# TempHumiditySensorRaspberryPi.net
KiCad netlist of a schematic drawn in EAGLE
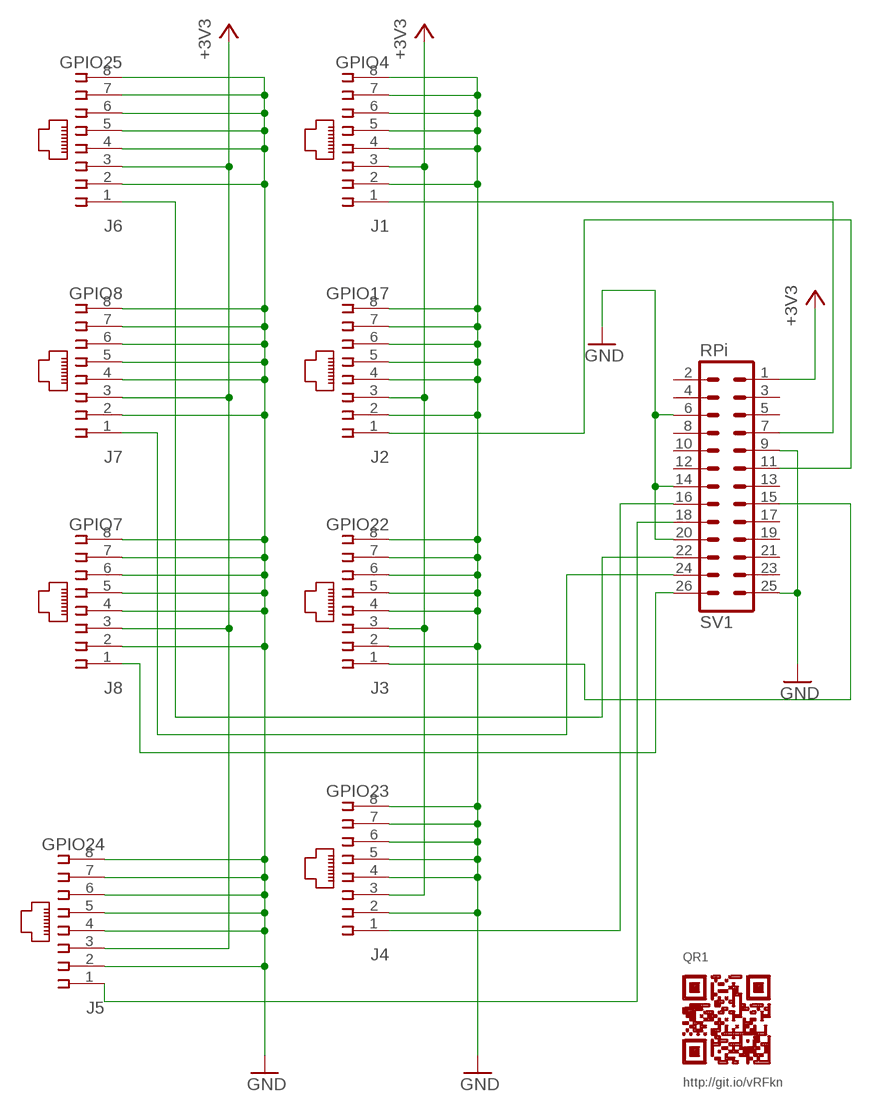
[diagram p0: schematic, sheet 1]

(export (version "E")
  (design (tool "Eeschema 10.0.6"))
  (components
    (comp (ref "J1")
      (value "GPIO4")
      (footprint "eagle-import:555164-1")
      (fields (field (name "PARTNO") "5555164-1"))
      (libsource (lib "eagle-import") (part "555164-1"))
    )
    (comp (ref "J2")
      (value "GPIO17")
      (footprint "eagle-import:555164-1")
      (fields (field (name "PARTNO") "5555164-1"))
      (libsource (lib "eagle-import") (part "555164-1"))
    )
    (comp (ref "J3")
      (value "GPIO22")
      (footprint "eagle-import:555164-1")
      (fields (field (name "PARTNO") "5555164-1"))
      (libsource (lib "eagle-import") (part "555164-1"))
    )
    (comp (ref "J4")
      (value "GPIO23")
      (footprint "eagle-import:555164-1")
      (fields (field (name "PARTNO") "5555164-1"))
      (libsource (lib "eagle-import") (part "555164-1"))
    )
    (comp (ref "J5")
      (value "GPIO24")
      (footprint "eagle-import:555164-1")
      (fields (field (name "PARTNO") "5555164-1"))
      (libsource (lib "eagle-import") (part "555164-1"))
    )
    (comp (ref "J6")
      (value "GPIO25")
      (footprint "eagle-import:555164-1")
      (fields (field (name "PARTNO") "5555164-1"))
      (libsource (lib "eagle-import") (part "555164-1"))
    )
    (comp (ref "J7")
      (value "GPIO8")
      (footprint "eagle-import:555164-1")
      (fields (field (name "PARTNO") "5555164-1"))
      (libsource (lib "eagle-import") (part "555164-1"))
    )
    (comp (ref "J8")
      (value "GPIO7")
      (footprint "eagle-import:555164-1")
      (fields (field (name "PARTNO") "5555164-1"))
      (libsource (lib "eagle-import") (part "555164-1"))
    )
    (comp (ref "QR1")
      (value "QR-HTTP://GIT.IO/VRFKN")
      (footprint "eagle-import:QR-HTTP___GIT.IO_VRFKN")
      (libsource (lib "eagle-import") (part "QR-HTTP{colon}//GIT.IO/VRFKN"))
    )
    (comp (ref "SV1")
      (value "RPi")
      (footprint "eagle-import:ML26")
      (fields (field (name "PARTNO") "SBH11-PBPC-D13-ST-BK"))
      (libsource (lib "eagle-import") (part "ML26"))
    )
  )
  (nets
    (net (code "1") (name "+3V3") (class "Default")
      (node (ref "J1") (pin "3") (pinfunction "3_3") (pintype "passive"))
      (node (ref "J2") (pin "3") (pinfunction "3_3") (pintype "passive"))
      (node (ref "J3") (pin "3") (pinfunction "3_3") (pintype "passive"))
      (node (ref "J4") (pin "3") (pinfunction "3_3") (pintype "passive"))
      (node (ref "J5") (pin "3") (pinfunction "3_3") (pintype "passive"))
      (node (ref "J6") (pin "3") (pinfunction "3_3") (pintype "passive"))
      (node (ref "J7") (pin "3") (pinfunction "3_3") (pintype "passive"))
      (node (ref "J8") (pin "3") (pinfunction "3_3") (pintype "passive"))
      (node (ref "SV1") (pin "1") (pinfunction "1_1") (pintype "passive"))
    )
    (net (code "2") (name "GND") (class "Default")
      (node (ref "J1") (pin "2") (pinfunction "2_2") (pintype "passive"))
      (node (ref "J1") (pin "4") (pinfunction "4_4") (pintype "passive"))
      (node (ref "J1") (pin "5") (pinfunction "5_5") (pintype "passive"))
      (node (ref "J1") (pin "6") (pinfunction "6_6") (pintype "passive"))
      (node (ref "J1") (pin "7") (pinfunction "7_7") (pintype "passive"))
      (node (ref "J1") (pin "8") (pinfunction "8_8") (pintype "passive"))
      (node (ref "J2") (pin "2") (pinfunction "2_2") (pintype "passive"))
      (node (ref "J2") (pin "4") (pinfunction "4_4") (pintype "passive"))
      (node (ref "J2") (pin "5") (pinfunction "5_5") (pintype "passive"))
      (node (ref "J2") (pin "6") (pinfunction "6_6") (pintype "passive"))
      (node (ref "J2") (pin "7") (pinfunction "7_7") (pintype "passive"))
      (node (ref "J2") (pin "8") (pinfunction "8_8") (pintype "passive"))
      (node (ref "J3") (pin "2") (pinfunction "2_2") (pintype "passive"))
      (node (ref "J3") (pin "4") (pinfunction "4_4") (pintype "passive"))
      (node (ref "J3") (pin "5") (pinfunction "5_5") (pintype "passive"))
      (node (ref "J3") (pin "6") (pinfunction "6_6") (pintype "passive"))
      (node (ref "J3") (pin "7") (pinfunction "7_7") (pintype "passive"))
      (node (ref "J3") (pin "8") (pinfunction "8_8") (pintype "passive"))
      (node (ref "J4") (pin "2") (pinfunction "2_2") (pintype "passive"))
      (node (ref "J4") (pin "4") (pinfunction "4_4") (pintype "passive"))
      (node (ref "J4") (pin "5") (pinfunction "5_5") (pintype "passive"))
      (node (ref "J4") (pin "6") (pinfunction "6_6") (pintype "passive"))
      (node (ref "J4") (pin "7") (pinfunction "7_7") (pintype "passive"))
      (node (ref "J4") (pin "8") (pinfunction "8_8") (pintype "passive"))
      (node (ref "J5") (pin "2") (pinfunction "2_2") (pintype "passive"))
      (node (ref "J5") (pin "4") (pinfunction "4_4") (pintype "passive"))
      (node (ref "J5") (pin "5") (pinfunction "5_5") (pintype "passive"))
      (node (ref "J5") (pin "6") (pinfunction "6_6") (pintype "passive"))
      (node (ref "J5") (pin "7") (pinfunction "7_7") (pintype "passive"))
      (node (ref "J5") (pin "8") (pinfunction "8_8") (pintype "passive"))
      (node (ref "J6") (pin "2") (pinfunction "2_2") (pintype "passive"))
      (node (ref "J6") (pin "4") (pinfunction "4_4") (pintype "passive"))
      (node (ref "J6") (pin "5") (pinfunction "5_5") (pintype "passive"))
      (node (ref "J6") (pin "6") (pinfunction "6_6") (pintype "passive"))
      (node (ref "J6") (pin "7") (pinfunction "7_7") (pintype "passive"))
      (node (ref "J6") (pin "8") (pinfunction "8_8") (pintype "passive"))
      (node (ref "J7") (pin "2") (pinfunction "2_2") (pintype "passive"))
      (node (ref "J7") (pin "4") (pinfunction "4_4") (pintype "passive"))
      (node (ref "J7") (pin "5") (pinfunction "5_5") (pintype "passive"))
      (node (ref "J7") (pin "6") (pinfunction "6_6") (pintype "passive"))
      (node (ref "J7") (pin "7") (pinfunction "7_7") (pintype "passive"))
      (node (ref "J7") (pin "8") (pinfunction "8_8") (pintype "passive"))
      (node (ref "J8") (pin "2") (pinfunction "2_2") (pintype "passive"))
      (node (ref "J8") (pin "4") (pinfunction "4_4") (pintype "passive"))
      (node (ref "J8") (pin "5") (pinfunction "5_5") (pintype "passive"))
      (node (ref "J8") (pin "6") (pinfunction "6_6") (pintype "passive"))
      (node (ref "J8") (pin "7") (pinfunction "7_7") (pintype "passive"))
      (node (ref "J8") (pin "8") (pinfunction "8_8") (pintype "passive"))
      (node (ref "SV1") (pin "14") (pinfunction "14_14") (pintype "passive"))
      (node (ref "SV1") (pin "20") (pinfunction "20_20") (pintype "passive"))
      (node (ref "SV1") (pin "25") (pinfunction "25_25") (pintype "passive"))
      (node (ref "SV1") (pin "6") (pinfunction "6_6") (pintype "passive"))
      (node (ref "SV1") (pin "9") (pinfunction "9_9") (pintype "passive"))
    )
    (net (code "3") (name "Net-(J1-Pad1)") (class "Default")
      (node (ref "J1") (pin "1") (pinfunction "1_1") (pintype "passive"))
      (node (ref "SV1") (pin "7") (pinfunction "7_7") (pintype "passive"))
    )
    (net (code "4") (name "Net-(J2-Pad1)") (class "Default")
      (node (ref "J2") (pin "1") (pinfunction "1_1") (pintype "passive"))
      (node (ref "SV1") (pin "11") (pinfunction "11_11") (pintype "passive"))
    )
    (net (code "5") (name "Net-(J3-Pad1)") (class "Default")
      (node (ref "J3") (pin "1") (pinfunction "1_1") (pintype "passive"))
      (node (ref "SV1") (pin "15") (pinfunction "15_15") (pintype "passive"))
    )
    (net (code "6") (name "Net-(J4-Pad1)") (class "Default")
      (node (ref "J4") (pin "1") (pinfunction "1_1") (pintype "passive"))
      (node (ref "SV1") (pin "16") (pinfunction "16_16") (pintype "passive"))
    )
    (net (code "7") (name "Net-(J5-Pad1)") (class "Default")
      (node (ref "J5") (pin "1") (pinfunction "1_1") (pintype "passive"))
      (node (ref "SV1") (pin "18") (pinfunction "18_18") (pintype "passive"))
    )
    (net (code "8") (name "Net-(J6-Pad1)") (class "Default")
      (node (ref "J6") (pin "1") (pinfunction "1_1") (pintype "passive"))
      (node (ref "SV1") (pin "22") (pinfunction "22_22") (pintype "passive"))
    )
    (net (code "9") (name "Net-(J7-Pad1)") (class "Default")
      (node (ref "J7") (pin "1") (pinfunction "1_1") (pintype "passive"))
      (node (ref "SV1") (pin "24") (pinfunction "24_24") (pintype "passive"))
    )
    (net (code "10") (name "Net-(J8-Pad1)") (class "Default")
      (node (ref "J8") (pin "1") (pinfunction "1_1") (pintype "passive"))
      (node (ref "SV1") (pin "26") (pinfunction "26_26") (pintype "passive"))
    )
    (net (code "11") (name "unconnected-(SV1-Pad2)") (class "Default")
      (node (ref "SV1") (pin "2") (pinfunction "2_2") (pintype "passive"))
    )
    (net (code "12") (name "unconnected-(SV1-Pad3)") (class "Default")
      (node (ref "SV1") (pin "3") (pinfunction "3_3") (pintype "passive"))
    )
    (net (code "13") (name "unconnected-(SV1-Pad4)") (class "Default")
      (node (ref "SV1") (pin "4") (pinfunction "4_4") (pintype "passive"))
    )
    (net (code "14") (name "unconnected-(SV1-Pad5)") (class "Default")
      (node (ref "SV1") (pin "5") (pinfunction "5_5") (pintype "passive"))
    )
    (net (code "15") (name "unconnected-(SV1-Pad8)") (class "Default")
      (node (ref "SV1") (pin "8") (pinfunction "8_8") (pintype "passive"))
    )
    (net (code "16") (name "unconnected-(SV1-Pad10)") (class "Default")
      (node (ref "SV1") (pin "10") (pinfunction "10_10") (pintype "passive"))
    )
    (net (code "17") (name "unconnected-(SV1-Pad12)") (class "Default")
      (node (ref "SV1") (pin "12") (pinfunction "12_12") (pintype "passive"))
    )
    (net (code "18") (name "unconnected-(SV1-Pad13)") (class "Default")
      (node (ref "SV1") (pin "13") (pinfunction "13_13") (pintype "passive"))
    )
    (net (code "19") (name "unconnected-(SV1-Pad17)") (class "Default")
      (node (ref "SV1") (pin "17") (pinfunction "17_17") (pintype "passive"))
    )
    (net (code "20") (name "unconnected-(SV1-Pad19)") (class "Default")
      (node (ref "SV1") (pin "19") (pinfunction "19_19") (pintype "passive"))
    )
    (net (code "21") (name "unconnected-(SV1-Pad21)") (class "Default")
      (node (ref "SV1") (pin "21") (pinfunction "21_21") (pintype "passive"))
    )
    (net (code "22") (name "unconnected-(SV1-Pad23)") (class "Default")
      (node (ref "SV1") (pin "23") (pinfunction "23_23") (pintype "passive"))
    )
  )
)
